# board_schem.net
KiCad netlist of a schematic drawn in EAGLE
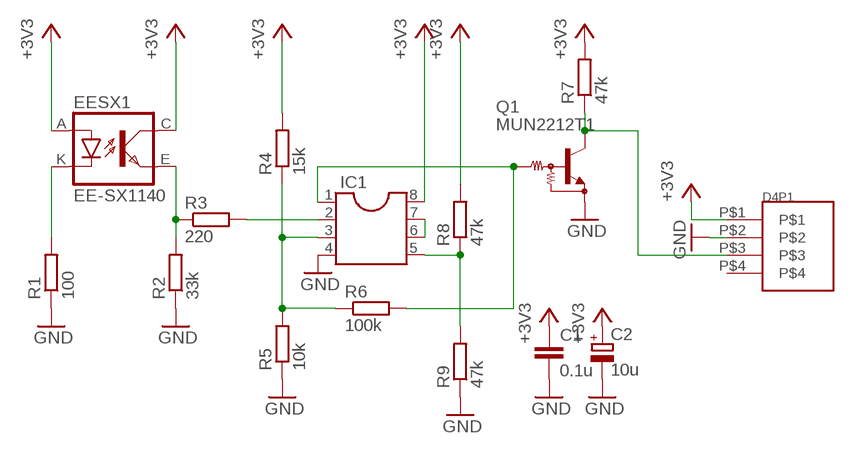
[diagram p0: schematic, sheet 1]

(export (version "E")
  (design (tool "Eeschema 10.0.6"))
  (components
    (comp (ref "C1")
      (value "0.1u")
      (footprint "eagle-import:C050-024X044")
      (libsource (lib "eagle-import") (part "C-EU050-024X044"))
    )
    (comp (ref "C2")
      (value "10u")
      (footprint "eagle-import:E2,5-5")
      (libsource (lib "eagle-import") (part "CPOL-EUE2.5-5"))
    )
    (comp (ref "D4P1")
      (value "DF1E-4P")
      (footprint "eagle-import:DF1E-4P")
      (libsource (lib "eagle-import") (part "DF1E-4P"))
    )
    (comp (ref "EESX1")
      (value "EE-SX1140")
      (footprint "eagle-import:EE-SX1140")
      (libsource (lib "eagle-import") (part "EE-SX1140"))
    )
    (comp (ref "IC1")
      (value "DIL8")
      (footprint "eagle-import:DIL08")
      (libsource (lib "eagle-import") (part "DIL8"))
    )
    (comp (ref "Q1")
      (value "MUN2212T1")
      (footprint "eagle-import:SC59-BEC")
      (libsource (lib "eagle-import") (part "MUN2212T1"))
    )
    (comp (ref "R1")
      (value "100")
      (footprint "eagle-import:0207_10")
      (libsource (lib "eagle-import") (part "R-EU_0207/10"))
    )
    (comp (ref "R2")
      (value "33k")
      (footprint "eagle-import:0207_10")
      (libsource (lib "eagle-import") (part "R-EU_0207/10"))
    )
    (comp (ref "R3")
      (value "220")
      (footprint "eagle-import:0207_10")
      (libsource (lib "eagle-import") (part "R-EU_0207/10"))
    )
    (comp (ref "R4")
      (value "15k")
      (footprint "eagle-import:0207_10")
      (libsource (lib "eagle-import") (part "R-EU_0207/10"))
    )
    (comp (ref "R5")
      (value "10k")
      (footprint "eagle-import:0207_10")
      (libsource (lib "eagle-import") (part "R-EU_0207/10"))
    )
    (comp (ref "R6")
      (value "100k")
      (footprint "eagle-import:0207_10")
      (libsource (lib "eagle-import") (part "R-EU_0207/10"))
    )
    (comp (ref "R7")
      (value "47k")
      (footprint "eagle-import:0207_10")
      (libsource (lib "eagle-import") (part "R-EU_0207/10"))
    )
    (comp (ref "R8")
      (value "47k")
      (footprint "eagle-import:0207_10")
      (libsource (lib "eagle-import") (part "R-EU_0207/10"))
    )
    (comp (ref "R9")
      (value "47k")
      (footprint "eagle-import:0207_10")
      (libsource (lib "eagle-import") (part "R-EU_0207/10"))
    )
  )
  (nets
    (net (code "1") (name "+3V3") (class "Default")
      (node (ref "C1") (pin "1") (pinfunction "1_1") (pintype "passive"))
      (node (ref "C2") (pin "+") (pinfunction "+_+") (pintype "passive"))
      (node (ref "D4P1") (pin "P$1") (pinfunction "P$1_P$1") (pintype "bidirectional"))
      (node (ref "EESX1") (pin "A") (pinfunction "A_A") (pintype "passive"))
      (node (ref "EESX1") (pin "C") (pinfunction "COL_C") (pintype "passive"))
      (node (ref "IC1") (pin "8") (pinfunction "8_8") (pintype "passive"))
      (node (ref "R4") (pin "2") (pinfunction "2_2") (pintype "passive"))
      (node (ref "R7") (pin "2") (pinfunction "2_2") (pintype "passive"))
      (node (ref "R8") (pin "2") (pinfunction "2_2") (pintype "passive"))
    )
    (net (code "2") (name "GND") (class "Default")
      (node (ref "C1") (pin "2") (pinfunction "2_2") (pintype "passive"))
      (node (ref "C2") (pin "-") (pinfunction "-_-") (pintype "passive"))
      (node (ref "D4P1") (pin "P$2") (pinfunction "P$2_P$2") (pintype "bidirectional"))
      (node (ref "IC1") (pin "4") (pinfunction "4_4") (pintype "passive"))
      (node (ref "Q1") (pin "E") (pinfunction "E_E") (pintype "passive"))
      (node (ref "R1") (pin "1") (pinfunction "1_1") (pintype "passive"))
      (node (ref "R2") (pin "1") (pinfunction "1_1") (pintype "passive"))
      (node (ref "R5") (pin "1") (pinfunction "1_1") (pintype "passive"))
      (node (ref "R9") (pin "1") (pinfunction "1_1") (pintype "passive"))
    )
    (net (code "3") (name "Net-(D4P1-PadP$3)") (class "Default")
      (node (ref "D4P1") (pin "P$3") (pinfunction "P$3_P$3") (pintype "bidirectional"))
      (node (ref "Q1") (pin "C") (pinfunction "C_C") (pintype "passive"))
      (node (ref "R7") (pin "1") (pinfunction "1_1") (pintype "passive"))
    )
    (net (code "4") (name "Net-(EESX1-C)") (class "Default")
      (node (ref "EESX1") (pin "K") (pinfunction "C_K") (pintype "passive"))
      (node (ref "R1") (pin "2") (pinfunction "2_2") (pintype "passive"))
    )
    (net (code "5") (name "Net-(EESX1-EMIT)") (class "Default")
      (node (ref "EESX1") (pin "E") (pinfunction "EMIT_E") (pintype "passive"))
      (node (ref "R2") (pin "2") (pinfunction "2_2") (pintype "passive"))
      (node (ref "R3") (pin "1") (pinfunction "1_1") (pintype "passive"))
    )
    (net (code "6") (name "Net-(IC1-Pad1)") (class "Default")
      (node (ref "IC1") (pin "1") (pinfunction "1_1") (pintype "passive"))
      (node (ref "Q1") (pin "B") (pinfunction "B_B") (pintype "passive"))
      (node (ref "R6") (pin "2") (pinfunction "2_2") (pintype "passive"))
    )
    (net (code "7") (name "Net-(IC1-Pad2)") (class "Default")
      (node (ref "IC1") (pin "2") (pinfunction "2_2") (pintype "passive"))
      (node (ref "R3") (pin "2") (pinfunction "2_2") (pintype "passive"))
    )
    (net (code "8") (name "Net-(IC1-Pad3)") (class "Default")
      (node (ref "IC1") (pin "3") (pinfunction "3_3") (pintype "passive"))
      (node (ref "R4") (pin "1") (pinfunction "1_1") (pintype "passive"))
      (node (ref "R5") (pin "2") (pinfunction "2_2") (pintype "passive"))
      (node (ref "R6") (pin "1") (pinfunction "1_1") (pintype "passive"))
    )
    (net (code "9") (name "Net-(IC1-Pad5)") (class "Default")
      (node (ref "IC1") (pin "5") (pinfunction "5_5") (pintype "passive"))
      (node (ref "R8") (pin "1") (pinfunction "1_1") (pintype "passive"))
      (node (ref "R9") (pin "2") (pinfunction "2_2") (pintype "passive"))
    )
    (net (code "10") (name "Net-(IC1-Pad6)") (class "Default")
      (node (ref "IC1") (pin "6") (pinfunction "6_6") (pintype "passive"))
      (node (ref "IC1") (pin "7") (pinfunction "7_7") (pintype "passive"))
    )
    (net (code "11") (name "unconnected-(D4P1-PadP$4)") (class "Default")
      (node (ref "D4P1") (pin "P$4") (pinfunction "P$4_P$4") (pintype "bidirectional"))
    )
  )
)
